# IMU_Sch.net
KiCad netlist of a schematic drawn in Altium Designer
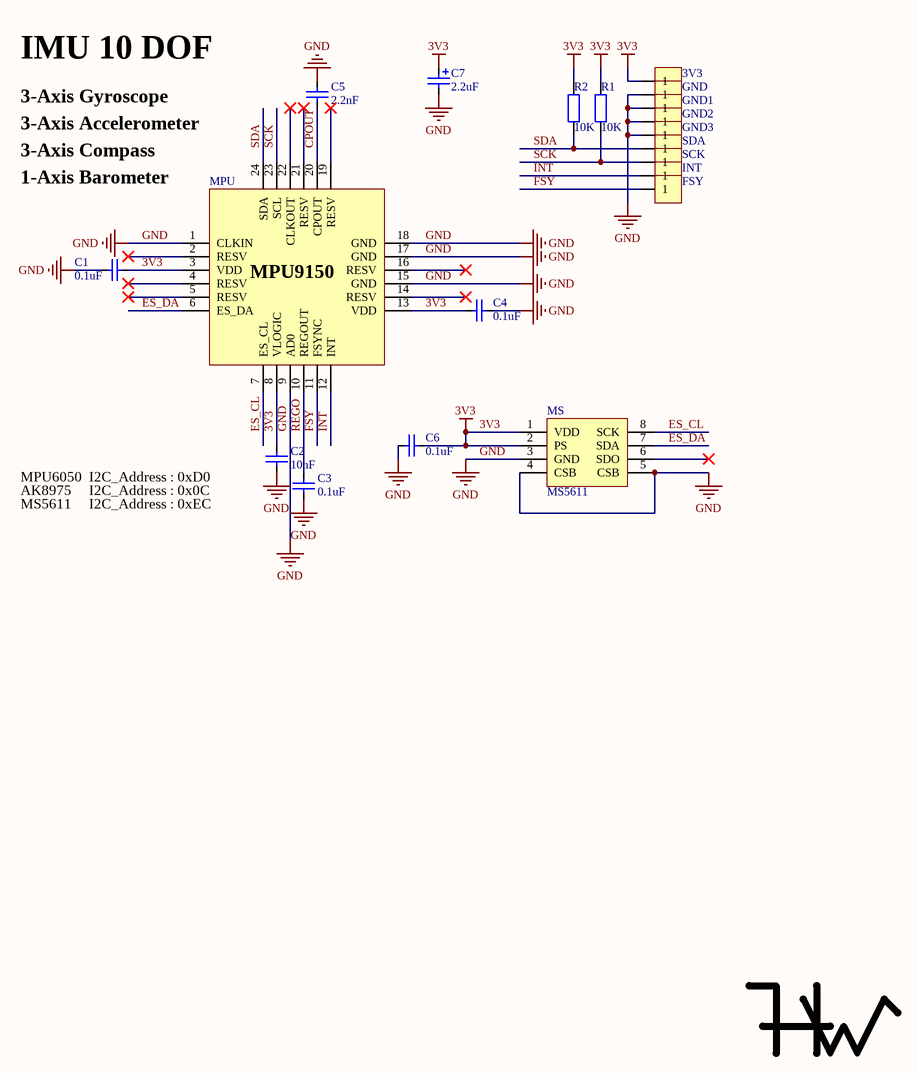
[diagram p0: IMU_Sch.SchDoc]

(export (version "E")
  (design (tool "Eeschema 10.0.6"))
  (components
    (comp (ref "3V3")
      (value "Pad1X1_1.27")
      (footprint "PCB_Connector:Pad1X1_1.27")
      (description "Header")
      (libsource (lib "SCH_Connector") (part "Pad1X1_1.27"))
    )
    (comp (ref "C1")
      (value "0.1uF")
      (footprint "PCB_Passive:CAP_0603")
      (description "Capacitor")
      (fields (field (name "Comment") "Cap_0603"))
      (libsource (lib "SCH_Passive") (part "Cap_0603"))
    )
    (comp (ref "C2")
      (value "10nF")
      (footprint "PCB_Passive:CAP_0603")
      (description "Capacitor")
      (fields (field (name "Comment") "Cap_0603"))
      (libsource (lib "SCH_Passive") (part "Cap_0603"))
    )
    (comp (ref "C3")
      (value "0.1uF")
      (footprint "PCB_Passive:CAP_0603")
      (description "Capacitor")
      (fields (field (name "Comment") "Cap_0603"))
      (libsource (lib "SCH_Passive") (part "Cap_0603"))
    )
    (comp (ref "C4")
      (value "0.1uF")
      (footprint "PCB_Passive:CAP_0603")
      (description "Capacitor")
      (fields (field (name "Comment") "Cap_0603"))
      (libsource (lib "SCH_Passive") (part "Cap_0603"))
    )
    (comp (ref "C5")
      (value "2.2nF")
      (footprint "PCB_Passive:CAP_0603")
      (description "Capacitor")
      (fields (field (name "Comment") "Cap_0603"))
      (libsource (lib "SCH_Passive") (part "Cap_0603"))
    )
    (comp (ref "C6")
      (value "0.1uF")
      (footprint "PCB_Passive:CAP_0603")
      (description "Capacitor")
      (fields (field (name "Comment") "Cap_0603"))
      (libsource (lib "SCH_Passive") (part "Cap_0603"))
    )
    (comp (ref "C7")
      (value "2.2uF")
      (footprint "PCB_Passive:CAP_TAN_P0805")
      (description "Capacitor")
      (fields (field (name "Comment") "Cap_Tan_0805"))
      (libsource (lib "SCH_Passive") (part "Cap_Tan_0805"))
    )
    (comp (ref "FSY")
      (value "Pad1X1_1.27")
      (footprint "PCB_Connector:Pad1X1_1.27")
      (description "Header")
      (libsource (lib "SCH_Connector") (part "Pad1X1_1.27"))
    )
    (comp (ref "GND")
      (value "Pad1X1_1.27")
      (footprint "PCB_Connector:Pad1X1_1.27")
      (description "Header")
      (libsource (lib "SCH_Connector") (part "Pad1X1_1.27"))
    )
    (comp (ref "GND1")
      (value "Pad1X1_1.27")
      (footprint "PCB_Connector:Pad1X1_1.27")
      (description "Header")
      (libsource (lib "SCH_Connector") (part "Pad1X1_1.27"))
    )
    (comp (ref "GND2")
      (value "Pad1X1_1.27")
      (footprint "PCB_Connector:Pad1X1_1.27")
      (description "Header")
      (libsource (lib "SCH_Connector") (part "Pad1X1_1.27"))
    )
    (comp (ref "GND3")
      (value "Pad1X1_1.27")
      (footprint "PCB_Connector:Pad1X1_1.27")
      (description "Header")
      (libsource (lib "SCH_Connector") (part "Pad1X1_1.27"))
    )
    (comp (ref "INT")
      (value "Pad1X1_1.27")
      (footprint "PCB_Connector:Pad1X1_1.27")
      (description "Header")
      (libsource (lib "SCH_Connector") (part "Pad1X1_1.27"))
    )
    (comp (ref "Mark") (value "Mark") (footprint "PCB_Logo:Logo_HW") (libsource (lib "SCH_Mark") (part "HW")))
    (comp (ref "MPU")
      (value "MPU9150")
      (footprint "PCB_IC:MPU9150")
      (description "Sensor")
      (libsource (lib "SCH_IC") (part "MPU9150"))
    )
    (comp (ref "MS")
      (value "MS5611")
      (footprint "MS5611")
      (description "Sensor")
      (libsource (lib "SCH_IC") (part "MS5611"))
    )
    (comp (ref "R1")
      (value "10K")
      (footprint "PCB_Passive:RES_0603")
      (description "Resistor")
      (fields (field (name "Comment") "Res_0603"))
      (libsource (lib "SCH_Passive") (part "Res_0603"))
    )
    (comp (ref "R2")
      (value "10K")
      (footprint "PCB_Passive:RES_0603")
      (description "Resistor")
      (fields (field (name "Comment") "Res_0603"))
      (libsource (lib "SCH_Passive") (part "Res_0603"))
    )
    (comp (ref "SCK")
      (value "Pad1X1_1.27")
      (footprint "PCB_Connector:Pad1X1_1.27")
      (description "Header")
      (libsource (lib "SCH_Connector") (part "Pad1X1_1.27"))
    )
    (comp (ref "SDA")
      (value "Pad1X1_1.27")
      (footprint "PCB_Connector:Pad1X1_1.27")
      (description "Header")
      (libsource (lib "SCH_Connector") (part "Pad1X1_1.27"))
    )
  )
  (nets
    (net (code "1") (name "/CPOUT") (class "Default")
      (node (ref "C5") (pin "1") (pinfunction "1_1") (pintype "passive"))
      (node (ref "MPU") (pin "20") (pinfunction "CPOUT_20") (pintype "passive"))
    )
    (net (code "2") (name "/ES_CL") (class "Default")
      (node (ref "MPU") (pin "7") (pinfunction "ES_CL_7") (pintype "passive"))
      (node (ref "MS") (pin "8") (pinfunction "SCK_8") (pintype "passive"))
    )
    (net (code "3") (name "/ES_DA") (class "Default")
      (node (ref "MPU") (pin "6") (pinfunction "ES_DA_6") (pintype "passive"))
      (node (ref "MS") (pin "7") (pinfunction "SDA_7") (pintype "passive"))
    )
    (net (code "4") (name "/FSY") (class "Default")
      (node (ref "FSY") (pin "1") (pinfunction "1_1") (pintype "passive"))
      (node (ref "MPU") (pin "11") (pinfunction "FSYNC_11") (pintype "passive"))
    )
    (net (code "5") (name "/INT") (class "Default")
      (node (ref "INT") (pin "1") (pinfunction "1_1") (pintype "passive"))
      (node (ref "MPU") (pin "12") (pinfunction "INT_12") (pintype "passive"))
    )
    (net (code "6") (name "/REGO") (class "Default")
      (node (ref "C3") (pin "2") (pinfunction "2_2") (pintype "passive"))
      (node (ref "MPU") (pin "10") (pinfunction "REGOUT_10") (pintype "passive"))
    )
    (net (code "7") (name "/SCK") (class "Default")
      (node (ref "MPU") (pin "23") (pinfunction "SCL_23") (pintype "passive"))
      (node (ref "R1") (pin "2") (pinfunction "2_2") (pintype "passive"))
      (node (ref "SCK") (pin "1") (pinfunction "1_1") (pintype "passive"))
    )
    (net (code "8") (name "/SDA") (class "Default")
      (node (ref "MPU") (pin "24") (pinfunction "SDA_24") (pintype "passive"))
      (node (ref "R2") (pin "2") (pinfunction "2_2") (pintype "passive"))
      (node (ref "SDA") (pin "1") (pinfunction "1_1") (pintype "passive"))
    )
    (net (code "9") (name "3V3") (class "Default")
      (node (ref "3V3") (pin "1") (pinfunction "1_1") (pintype "passive"))
      (node (ref "C1") (pin "2") (pinfunction "2_2") (pintype "passive"))
      (node (ref "C2") (pin "2") (pinfunction "2_2") (pintype "passive"))
      (node (ref "C4") (pin "2") (pinfunction "2_2") (pintype "passive"))
      (node (ref "C6") (pin "1") (pinfunction "1_1") (pintype "passive"))
      (node (ref "C7") (pin "1") (pinfunction "1_1") (pintype "passive"))
      (node (ref "MPU") (pin "13") (pinfunction "VDD_13") (pintype "passive"))
      (node (ref "MPU") (pin "3") (pinfunction "VDD_3") (pintype "passive"))
      (node (ref "MPU") (pin "8") (pinfunction "VLOGIC_8") (pintype "passive"))
      (node (ref "MS") (pin "1") (pinfunction "VDD_1") (pintype "passive"))
      (node (ref "MS") (pin "2") (pinfunction "PS_2") (pintype "passive"))
      (node (ref "R1") (pin "1") (pinfunction "1_1") (pintype "passive"))
      (node (ref "R2") (pin "1") (pinfunction "1_1") (pintype "passive"))
    )
    (net (code "10") (name "GND") (class "Default")
      (node (ref "C1") (pin "1") (pinfunction "1_1") (pintype "passive"))
      (node (ref "C2") (pin "1") (pinfunction "1_1") (pintype "passive"))
      (node (ref "C3") (pin "1") (pinfunction "1_1") (pintype "passive"))
      (node (ref "C4") (pin "1") (pinfunction "1_1") (pintype "passive"))
      (node (ref "C5") (pin "2") (pinfunction "2_2") (pintype "passive"))
      (node (ref "C6") (pin "2") (pinfunction "2_2") (pintype "passive"))
      (node (ref "C7") (pin "2") (pinfunction "2_2") (pintype "passive"))
      (node (ref "GND") (pin "1") (pinfunction "1_1") (pintype "passive"))
      (node (ref "GND1") (pin "1") (pinfunction "1_1") (pintype "passive"))
      (node (ref "GND2") (pin "1") (pinfunction "1_1") (pintype "passive"))
      (node (ref "GND3") (pin "1") (pinfunction "1_1") (pintype "passive"))
      (node (ref "MPU") (pin "1") (pinfunction "CLKIN_1") (pintype "passive"))
      (node (ref "MPU") (pin "15") (pinfunction "GND_15") (pintype "passive"))
      (node (ref "MPU") (pin "17") (pinfunction "GND_17") (pintype "passive"))
      (node (ref "MPU") (pin "18") (pinfunction "GND_18") (pintype "passive"))
      (node (ref "MPU") (pin "9") (pinfunction "AD0_9") (pintype "passive"))
      (node (ref "MS") (pin "3") (pinfunction "GND_3") (pintype "passive"))
      (node (ref "MS") (pin "4") (pinfunction "CSB_4") (pintype "passive"))
      (node (ref "MS") (pin "5") (pinfunction "CSB_5") (pintype "passive"))
    )
    (net (code "11") (name "unconnected-(MPU-CLKOUT-Pad22)") (class "Default")
      (node (ref "MPU") (pin "22") (pinfunction "CLKOUT_22") (pintype "passive+no_connect"))
    )
    (net (code "12") (name "unconnected-(MPU-RESV-Pad2)") (class "Default")
      (node (ref "MPU") (pin "2") (pinfunction "RESV_2") (pintype "passive+no_connect"))
    )
    (net (code "13") (name "unconnected-(MPU-RESV-Pad4)") (class "Default")
      (node (ref "MPU") (pin "4") (pinfunction "RESV_4") (pintype "passive+no_connect"))
    )
    (net (code "14") (name "unconnected-(MPU-RESV-Pad5)") (class "Default")
      (node (ref "MPU") (pin "5") (pinfunction "RESV_5") (pintype "passive+no_connect"))
    )
    (net (code "15") (name "unconnected-(MPU-RESV-Pad14)") (class "Default")
      (node (ref "MPU") (pin "14") (pinfunction "RESV_14") (pintype "passive+no_connect"))
    )
    (net (code "16") (name "unconnected-(MPU-RESV-Pad16)") (class "Default")
      (node (ref "MPU") (pin "16") (pinfunction "RESV_16") (pintype "passive+no_connect"))
    )
    (net (code "17") (name "unconnected-(MPU-RESV-Pad19)") (class "Default")
      (node (ref "MPU") (pin "19") (pinfunction "RESV_19") (pintype "passive+no_connect"))
    )
    (net (code "18") (name "unconnected-(MPU-RESV-Pad21)") (class "Default")
      (node (ref "MPU") (pin "21") (pinfunction "RESV_21") (pintype "passive+no_connect"))
    )
    (net (code "19") (name "unconnected-(MS-SDO-Pad6)") (class "Default")
      (node (ref "MS") (pin "6") (pinfunction "SDO_6") (pintype "passive+no_connect"))
    )
  )
)
